# ep_board.net
KiCad netlist of a schematic drawn in EAGLE
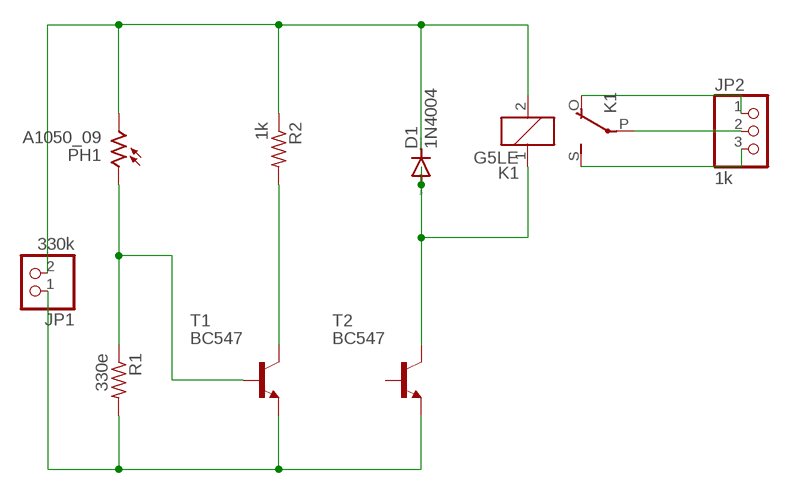
[diagram p0: schematic, sheet 1]

(export (version "E")
  (design (tool "Eeschema 10.0.6"))
  (components
    (comp (ref "D1")
      (value "1N4004")
      (footprint "eagle-import:DO41-10")
      (libsource (lib "eagle-import") (part "1N4004"))
    )
    (comp (ref "JP1")
      (value "330k")
      (footprint "eagle-import:1X02")
      (libsource (lib "eagle-import") (part "PINHD-1X2"))
    )
    (comp (ref "JP2")
      (value "1k")
      (footprint "eagle-import:1X03")
      (libsource (lib "eagle-import") (part "PINHD-1X3"))
    )
    (comp (ref "K1")
      (value "G5LE")
      (footprint "eagle-import:G5LE")
      (libsource (lib "eagle-import") (part "G5LE"))
    )
    (comp (ref "PH1")
      (value "A1050_09")
      (footprint "eagle-import:T0-46-A10XX")
      (libsource (lib "eagle-import") (part "A1050_09"))
    )
    (comp (ref "R1")
      (value "330e")
      (footprint "eagle-import:0207_10")
      (libsource (lib "eagle-import") (part "R-US_0207/10"))
    )
    (comp (ref "R2")
      (value "1k")
      (footprint "eagle-import:0207_10")
      (libsource (lib "eagle-import") (part "R-US_0207/10"))
    )
    (comp (ref "T1")
      (value "BC547")
      (footprint "eagle-import:TO92")
      (libsource (lib "eagle-import") (part "BC547"))
    )
    (comp (ref "T2")
      (value "BC547")
      (footprint "eagle-import:TO92")
      (libsource (lib "eagle-import") (part "BC547"))
    )
  )
  (nets
    (net (code "1") (name "Net-(D1-PadC)") (class "Default")
      (node (ref "D1") (pin "C") (pinfunction "C_C") (pintype "passive"))
      (node (ref "JP1") (pin "2") (pinfunction "2_2") (pintype "passive"))
      (node (ref "K1") (pin "2") (pinfunction "2_2") (pintype "passive"))
      (node (ref "PH1") (pin "2") (pinfunction "2_2") (pintype "passive"))
      (node (ref "R2") (pin "1") (pinfunction "1_1") (pintype "passive"))
    )
    (net (code "2") (name "Net-(JP2-Pad1)") (class "Default")
      (node (ref "JP2") (pin "1") (pinfunction "1_1") (pintype "passive"))
      (node (ref "K1") (pin "O") (pinfunction "O_O") (pintype "passive"))
    )
    (net (code "3") (name "Net-(JP2-Pad2)") (class "Default")
      (node (ref "JP2") (pin "2") (pinfunction "2_2") (pintype "passive"))
      (node (ref "K1") (pin "P") (pinfunction "P_P") (pintype "passive"))
    )
    (net (code "4") (name "Net-(JP2-Pad3)") (class "Default")
      (node (ref "JP2") (pin "3") (pinfunction "3_3") (pintype "passive"))
      (node (ref "K1") (pin "S") (pinfunction "S_S") (pintype "passive"))
    )
    (net (code "5") (name "Net-(T1-B)") (class "Default")
      (node (ref "PH1") (pin "1") (pinfunction "1_1") (pintype "passive"))
      (node (ref "R1") (pin "1") (pinfunction "1_1") (pintype "passive"))
      (node (ref "T1") (pin "2") (pinfunction "B_2") (pintype "passive"))
    )
    (net (code "6") (name "Net-(T1-C)") (class "Default")
      (node (ref "R2") (pin "2") (pinfunction "2_2") (pintype "passive"))
      (node (ref "T1") (pin "3") (pinfunction "C_3") (pintype "passive"))
    )
    (net (code "7") (name "Net-(T1-E)") (class "Default")
      (node (ref "JP1") (pin "1") (pinfunction "1_1") (pintype "passive"))
      (node (ref "R1") (pin "2") (pinfunction "2_2") (pintype "passive"))
      (node (ref "T1") (pin "1") (pinfunction "E_1") (pintype "passive"))
      (node (ref "T2") (pin "1") (pinfunction "E_1") (pintype "passive"))
    )
    (net (code "8") (name "Net-(T2-C)") (class "Default")
      (node (ref "D1") (pin "A") (pinfunction "A_A") (pintype "passive"))
      (node (ref "K1") (pin "1") (pinfunction "1_1") (pintype "passive"))
      (node (ref "T2") (pin "3") (pinfunction "C_3") (pintype "passive"))
    )
    (net (code "9") (name "unconnected-(T2-B-Pad2)") (class "Default")
      (node (ref "T2") (pin "2") (pinfunction "B_2") (pintype "passive"))
    )
  )
)
